# PR5005V1_3.net
KiCad netlist of a schematic drawn in EAGLE
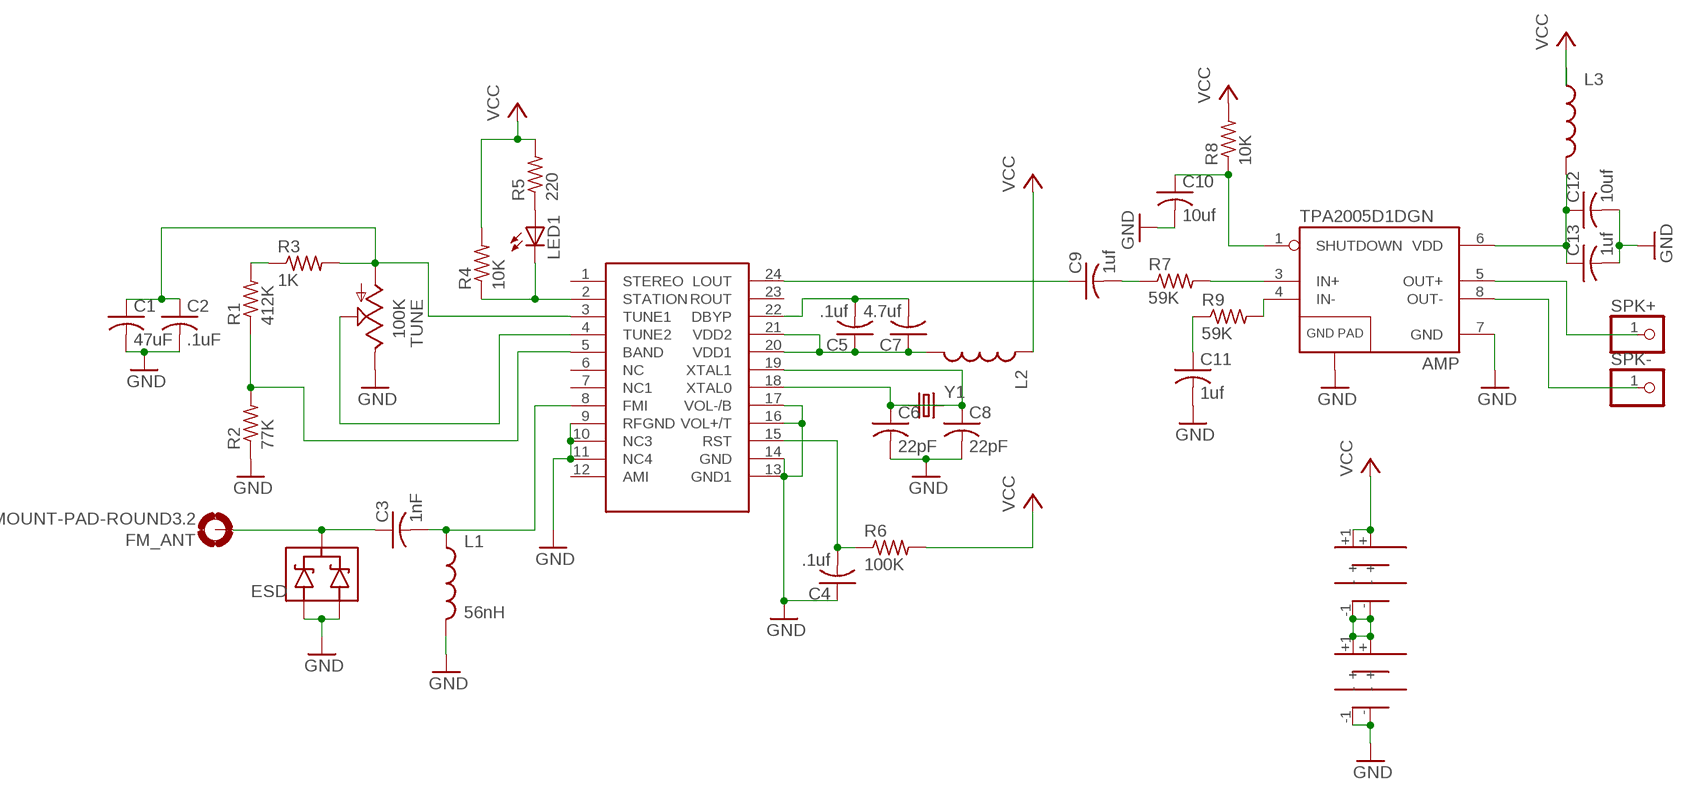
[diagram p0: schematic, sheet 1]

(export (version "E")
  (design (tool "Eeschema 10.0.6"))
  (components
    (comp (ref "AMP")
      (value "TPA2005D1DGN")
      (footprint "eagle-import:POWER-SOP8")
      (libsource (lib "eagle-import") (part "TPA2005D1DGN"))
    )
    (comp (ref "C1")
      (value "47uF")
      (footprint "eagle-import:C0603")
      (libsource (lib "eagle-import") (part "C-USC0603"))
    )
    (comp (ref "C2")
      (value ".1uF")
      (footprint "eagle-import:C0603")
      (libsource (lib "eagle-import") (part "C-USC0603"))
    )
    (comp (ref "C3")
      (value "1nF")
      (footprint "eagle-import:C0603")
      (libsource (lib "eagle-import") (part "C-USC0603"))
    )
    (comp (ref "C4")
      (value ".1uf")
      (footprint "eagle-import:C0603")
      (libsource (lib "eagle-import") (part "C-USC0603"))
    )
    (comp (ref "C5")
      (value ".1uf")
      (footprint "eagle-import:C0603")
      (libsource (lib "eagle-import") (part "C-USC0603"))
    )
    (comp (ref "C6")
      (value "22pF")
      (footprint "eagle-import:C0603")
      (libsource (lib "eagle-import") (part "C-USC0603"))
    )
    (comp (ref "C7")
      (value "4.7uf")
      (footprint "eagle-import:C0603")
      (libsource (lib "eagle-import") (part "C-USC0603"))
    )
    (comp (ref "C8")
      (value "22pF")
      (footprint "eagle-import:C0603")
      (libsource (lib "eagle-import") (part "C-USC0603"))
    )
    (comp (ref "C9")
      (value "1uf")
      (footprint "eagle-import:C0603")
      (libsource (lib "eagle-import") (part "C-USC0603"))
    )
    (comp (ref "C10")
      (value "10uf")
      (footprint "eagle-import:C0603")
      (libsource (lib "eagle-import") (part "C-USC0603"))
    )
    (comp (ref "C11")
      (value "1uf")
      (footprint "eagle-import:C0603")
      (libsource (lib "eagle-import") (part "C-USC0603"))
    )
    (comp (ref "C12")
      (value "10uf")
      (footprint "eagle-import:C0603")
      (libsource (lib "eagle-import") (part "C-USC0603"))
    )
    (comp (ref "C13")
      (value "1uf")
      (footprint "eagle-import:C0603")
      (libsource (lib "eagle-import") (part "C-USC0603"))
    )
    (comp (ref "ESD")
      (value "MMBZ27VCLT1")
      (footprint "eagle-import:SOT23-3")
      (libsource (lib "eagle-import") (part "MMBZ27VCLT1"))
    )
    (comp (ref "FM_ANT")
      (value "MOUNT-PAD-ROUND3.2")
      (footprint "eagle-import:3,2-PAD")
      (libsource (lib "eagle-import") (part "MOUNT-PAD-ROUND3.2"))
    )
    (comp (ref "L1")
      (value "56nH")
      (footprint "eagle-import:0603")
      (libsource (lib "eagle-import") (part "INDUCTOR0603"))
    )
    (comp (ref "L2")
      (value "INDUCTOR0603")
      (footprint "eagle-import:0603")
      (libsource (lib "eagle-import") (part "INDUCTOR0603"))
    )
    (comp (ref "L3")
      (value "INDUCTOR0603")
      (footprint "eagle-import:0603")
      (libsource (lib "eagle-import") (part "INDUCTOR0603"))
    )
    (comp (ref "LED1")
      (value "LEDCHIP-LED0603")
      (footprint "eagle-import:CHIP-LED0603")
      (libsource (lib "eagle-import") (part "LEDCHIP-LED0603"))
    )
    (comp (ref "R1")
      (value "412K")
      (footprint "eagle-import:R0603")
      (libsource (lib "eagle-import") (part "R-US_R0603"))
    )
    (comp (ref "R2")
      (value "77K")
      (footprint "eagle-import:R0603")
      (libsource (lib "eagle-import") (part "R-US_R0603"))
    )
    (comp (ref "R3")
      (value "1K")
      (footprint "eagle-import:R0603")
      (libsource (lib "eagle-import") (part "R-US_R0603"))
    )
    (comp (ref "R4")
      (value "10K")
      (footprint "eagle-import:R0603")
      (libsource (lib "eagle-import") (part "R-US_R0603"))
    )
    (comp (ref "R5")
      (value "220")
      (footprint "eagle-import:R0603")
      (libsource (lib "eagle-import") (part "R-US_R0603"))
    )
    (comp (ref "R6")
      (value "100K")
      (footprint "eagle-import:R0603")
      (libsource (lib "eagle-import") (part "R-US_R0603"))
    )
    (comp (ref "R7")
      (value "59K")
      (footprint "eagle-import:R0603")
      (libsource (lib "eagle-import") (part "R-US_R0603"))
    )
    (comp (ref "R8")
      (value "10K")
      (footprint "eagle-import:R0603")
      (libsource (lib "eagle-import") (part "R-US_R0603"))
    )
    (comp (ref "R9")
      (value "59K")
      (footprint "eagle-import:R0603")
      (libsource (lib "eagle-import") (part "R-US_R0603"))
    )
    (comp (ref "SI1")
      (value "SI4831-SSOP-24")
      (footprint "eagle-import:SI4831-SSOP-24")
      (libsource (lib "eagle-import") (part "SI4831-SSOP-24"))
    )
    (comp (ref "SPK+")
      (value "PINHD-1X1")
      (footprint "eagle-import:1X01")
      (libsource (lib "eagle-import") (part "PINHD-1X1"))
    )
    (comp (ref "SPK-")
      (value "PINHD-1X1")
      (footprint "eagle-import:1X01")
      (libsource (lib "eagle-import") (part "PINHD-1X1"))
    )
    (comp (ref "TUNE")
      (value "100K")
      (footprint "eagle-import:6MM")
      (libsource (lib "eagle-import") (part "TRIM"))
    )
    (comp (ref "U$1")
      (value "MPD-BK-92-AA-CLIP")
      (footprint "eagle-import:MPD-BK-92-AA-CLIP")
      (libsource (lib "eagle-import") (part "MPD-BK-92-AA-CLIP"))
    )
    (comp (ref "U$2")
      (value "MPD-BK-92-AA-CLIP")
      (footprint "eagle-import:MPD-BK-92-AA-CLIP")
      (libsource (lib "eagle-import") (part "MPD-BK-92-AA-CLIP"))
    )
    (comp (ref "Y1")
      (value "CRYSTAL32-SMD")
      (footprint "eagle-import:CRYSTAL-32KHZ-SMD")
      (libsource (lib "eagle-import") (part "CRYSTAL32-SMD"))
    )
  )
  (nets
    (net (code "1") (name "GND") (class "Default")
      (node (ref "AMP") (pin "7") (pinfunction "GND_7") (pintype "power_in"))
      (node (ref "AMP") (pin "9") (pinfunction "GND_9") (pintype "power_in"))
      (node (ref "C1") (pin "2") (pinfunction "2_2") (pintype "passive"))
      (node (ref "C10") (pin "2") (pinfunction "2_2") (pintype "passive"))
      (node (ref "C11") (pin "2") (pinfunction "2_2") (pintype "passive"))
      (node (ref "C12") (pin "2") (pinfunction "2_2") (pintype "passive"))
      (node (ref "C13") (pin "2") (pinfunction "2_2") (pintype "passive"))
      (node (ref "C2") (pin "2") (pinfunction "2_2") (pintype "passive"))
      (node (ref "C4") (pin "1") (pinfunction "1_1") (pintype "passive"))
      (node (ref "C6") (pin "2") (pinfunction "2_2") (pintype "passive"))
      (node (ref "C8") (pin "2") (pinfunction "2_2") (pintype "passive"))
      (node (ref "ESD") (pin "1") (pinfunction "A1_1") (pintype "passive"))
      (node (ref "ESD") (pin "2") (pinfunction "A2_2") (pintype "passive"))
      (node (ref "L1") (pin "2") (pinfunction "2_2") (pintype "passive"))
      (node (ref "R2") (pin "1") (pinfunction "1_1") (pintype "passive"))
      (node (ref "SI1") (pin "10") (pinfunction "NC3_10") (pintype "bidirectional"))
      (node (ref "SI1") (pin "11") (pinfunction "NC4_11") (pintype "bidirectional"))
      (node (ref "SI1") (pin "13") (pinfunction "GND1_13") (pintype "bidirectional"))
      (node (ref "SI1") (pin "14") (pinfunction "GND_14") (pintype "bidirectional"))
      (node (ref "SI1") (pin "16") (pinfunction "VOL+/T_16") (pintype "bidirectional"))
      (node (ref "SI1") (pin "17") (pinfunction "VOL-/B_17") (pintype "bidirectional"))
      (node (ref "SI1") (pin "9") (pinfunction "RFGND_9") (pintype "bidirectional"))
      (node (ref "TUNE") (pin "E") (pinfunction "E_E") (pintype "passive"))
      (node (ref "U$2") (pin "-") (pinfunction "-_-") (pintype "bidirectional"))
      (node (ref "U$2") (pin "-1") (pinfunction "-_-1") (pintype "bidirectional"))
    )
    (net (code "2") (name "Net-(AMP-IN+)") (class "Default")
      (node (ref "AMP") (pin "3") (pinfunction "IN+_3") (pintype "bidirectional"))
      (node (ref "R7") (pin "2") (pinfunction "2_2") (pintype "passive"))
    )
    (net (code "3") (name "Net-(AMP-IN-)") (class "Default")
      (node (ref "AMP") (pin "4") (pinfunction "IN-_4") (pintype "bidirectional"))
      (node (ref "R9") (pin "2") (pinfunction "2_2") (pintype "passive"))
    )
    (net (code "4") (name "Net-(AMP-OUT+)") (class "Default")
      (node (ref "AMP") (pin "5") (pinfunction "OUT+_5") (pintype "bidirectional"))
      (node (ref "SPK+") (pin "1") (pinfunction "1_1") (pintype "passive"))
    )
    (net (code "5") (name "Net-(AMP-OUT-)") (class "Default")
      (node (ref "AMP") (pin "8") (pinfunction "OUT-_8") (pintype "bidirectional"))
      (node (ref "SPK-") (pin "1") (pinfunction "1_1") (pintype "passive"))
    )
    (net (code "6") (name "Net-(AMP-SHUTDOWN)") (class "Default")
      (node (ref "AMP") (pin "1") (pinfunction "SHUTDOWN_1") (pintype "input"))
      (node (ref "C10") (pin "1") (pinfunction "1_1") (pintype "passive"))
      (node (ref "R8") (pin "1") (pinfunction "1_1") (pintype "passive"))
    )
    (net (code "7") (name "Net-(AMP-VDD)") (class "Default")
      (node (ref "AMP") (pin "6") (pinfunction "VDD_6") (pintype "power_in"))
      (node (ref "C12") (pin "1") (pinfunction "1_1") (pintype "passive"))
      (node (ref "C13") (pin "1") (pinfunction "1_1") (pintype "passive"))
      (node (ref "L3") (pin "2") (pinfunction "2_2") (pintype "passive"))
    )
    (net (code "8") (name "Net-(C9-Pad2)") (class "Default")
      (node (ref "C9") (pin "2") (pinfunction "2_2") (pintype "passive"))
      (node (ref "R7") (pin "1") (pinfunction "1_1") (pintype "passive"))
    )
    (net (code "9") (name "Net-(C11-Pad1)") (class "Default")
      (node (ref "C11") (pin "1") (pinfunction "1_1") (pintype "passive"))
      (node (ref "R9") (pin "1") (pinfunction "1_1") (pintype "passive"))
    )
    (net (code "10") (name "Net-(ESD-C)") (class "Default")
      (node (ref "C3") (pin "1") (pinfunction "1_1") (pintype "passive"))
      (node (ref "ESD") (pin "3") (pinfunction "C_3") (pintype "passive"))
      (node (ref "FM_ANT") (pin "B3,2") (pinfunction "MOUNT_B3,2") (pintype "passive"))
    )
    (net (code "11") (name "Net-(LED1-PadA)") (class "Default")
      (node (ref "LED1") (pin "A") (pinfunction "A_A") (pintype "passive"))
      (node (ref "R5") (pin "1") (pinfunction "1_1") (pintype "passive"))
    )
    (net (code "12") (name "Net-(R1-Pad2)") (class "Default")
      (node (ref "R1") (pin "2") (pinfunction "2_2") (pintype "passive"))
      (node (ref "R3") (pin "1") (pinfunction "1_1") (pintype "passive"))
    )
    (net (code "13") (name "Net-(SI1-BAND)") (class "Default")
      (node (ref "R1") (pin "1") (pinfunction "1_1") (pintype "passive"))
      (node (ref "R2") (pin "2") (pinfunction "2_2") (pintype "passive"))
      (node (ref "SI1") (pin "5") (pinfunction "BAND_5") (pintype "bidirectional"))
    )
    (net (code "14") (name "Net-(SI1-DBYP)") (class "Default")
      (node (ref "C5") (pin "2") (pinfunction "2_2") (pintype "passive"))
      (node (ref "C7") (pin "2") (pinfunction "2_2") (pintype "passive"))
      (node (ref "SI1") (pin "22") (pinfunction "DBYP_22") (pintype "bidirectional"))
    )
    (net (code "15") (name "Net-(SI1-FMI)") (class "Default")
      (node (ref "C3") (pin "2") (pinfunction "2_2") (pintype "passive"))
      (node (ref "L1") (pin "1") (pinfunction "1_1") (pintype "passive"))
      (node (ref "SI1") (pin "8") (pinfunction "FMI_8") (pintype "bidirectional"))
    )
    (net (code "16") (name "Net-(SI1-LOUT)") (class "Default")
      (node (ref "C9") (pin "1") (pinfunction "1_1") (pintype "passive"))
      (node (ref "SI1") (pin "24") (pinfunction "LOUT_24") (pintype "bidirectional"))
    )
    (net (code "17") (name "Net-(SI1-RST)") (class "Default")
      (node (ref "C4") (pin "2") (pinfunction "2_2") (pintype "passive"))
      (node (ref "R6") (pin "1") (pinfunction "1_1") (pintype "passive"))
      (node (ref "SI1") (pin "15") (pinfunction "RST_15") (pintype "bidirectional"))
    )
    (net (code "18") (name "Net-(SI1-STATION)") (class "Default")
      (node (ref "LED1") (pin "C") (pinfunction "C_C") (pintype "passive"))
      (node (ref "R4") (pin "1") (pinfunction "1_1") (pintype "passive"))
      (node (ref "SI1") (pin "2") (pinfunction "STATION_2") (pintype "bidirectional"))
    )
    (net (code "19") (name "Net-(SI1-TUNE1)") (class "Default")
      (node (ref "C1") (pin "1") (pinfunction "1_1") (pintype "passive"))
      (node (ref "C2") (pin "1") (pinfunction "1_1") (pintype "passive"))
      (node (ref "R3") (pin "2") (pinfunction "2_2") (pintype "passive"))
      (node (ref "SI1") (pin "3") (pinfunction "TUNE1_3") (pintype "bidirectional"))
      (node (ref "TUNE") (pin "A") (pinfunction "A_A") (pintype "passive"))
    )
    (net (code "20") (name "Net-(SI1-TUNE2)") (class "Default")
      (node (ref "SI1") (pin "4") (pinfunction "TUNE2_4") (pintype "bidirectional"))
      (node (ref "TUNE") (pin "S") (pinfunction "S_S") (pintype "passive"))
    )
    (net (code "21") (name "Net-(SI1-VDD1)") (class "Default")
      (node (ref "C5") (pin "1") (pinfunction "1_1") (pintype "passive"))
      (node (ref "C7") (pin "1") (pinfunction "1_1") (pintype "passive"))
      (node (ref "L2") (pin "2") (pinfunction "2_2") (pintype "passive"))
      (node (ref "SI1") (pin "20") (pinfunction "VDD1_20") (pintype "bidirectional"))
      (node (ref "SI1") (pin "21") (pinfunction "VDD2_21") (pintype "bidirectional"))
    )
    (net (code "22") (name "Net-(SI1-XTAL0)") (class "Default")
      (node (ref "C6") (pin "1") (pinfunction "1_1") (pintype "passive"))
      (node (ref "SI1") (pin "18") (pinfunction "XTAL0_18") (pintype "bidirectional"))
      (node (ref "Y1") (pin "X2") (pinfunction "2_X2") (pintype "passive"))
    )
    (net (code "23") (name "Net-(SI1-XTAL1)") (class "Default")
      (node (ref "C8") (pin "1") (pinfunction "1_1") (pintype "passive"))
      (node (ref "SI1") (pin "19") (pinfunction "XTAL1_19") (pintype "bidirectional"))
      (node (ref "Y1") (pin "X1") (pinfunction "1_X1") (pintype "passive"))
    )
    (net (code "24") (name "Net-(U$1---Pad-1)") (class "Default")
      (node (ref "U$1") (pin "-") (pinfunction "-_-") (pintype "bidirectional"))
      (node (ref "U$1") (pin "-1") (pinfunction "-_-1") (pintype "bidirectional"))
      (node (ref "U$2") (pin "+") (pinfunction "+_+") (pintype "bidirectional"))
      (node (ref "U$2") (pin "+1") (pinfunction "+_+1") (pintype "bidirectional"))
    )
    (net (code "25") (name "VCC") (class "Default")
      (node (ref "L2") (pin "1") (pinfunction "1_1") (pintype "passive"))
      (node (ref "L3") (pin "1") (pinfunction "1_1") (pintype "passive"))
      (node (ref "R4") (pin "2") (pinfunction "2_2") (pintype "passive"))
      (node (ref "R5") (pin "2") (pinfunction "2_2") (pintype "passive"))
      (node (ref "R6") (pin "2") (pinfunction "2_2") (pintype "passive"))
      (node (ref "R8") (pin "2") (pinfunction "2_2") (pintype "passive"))
      (node (ref "U$1") (pin "+") (pinfunction "+_+") (pintype "bidirectional"))
      (node (ref "U$1") (pin "+1") (pinfunction "+_+1") (pintype "bidirectional"))
    )
    (net (code "26") (name "unconnected-(SI1-AMI-Pad12)") (class "Default")
      (node (ref "SI1") (pin "12") (pinfunction "AMI_12") (pintype "bidirectional"))
    )
    (net (code "27") (name "unconnected-(SI1-NC-Pad6)") (class "Default")
      (node (ref "SI1") (pin "6") (pinfunction "NC_6") (pintype "bidirectional"))
    )
    (net (code "28") (name "unconnected-(SI1-NC1-Pad7)") (class "Default")
      (node (ref "SI1") (pin "7") (pinfunction "NC1_7") (pintype "bidirectional"))
    )
    (net (code "29") (name "unconnected-(SI1-ROUT-Pad23)") (class "Default")
      (node (ref "SI1") (pin "23") (pinfunction "ROUT_23") (pintype "bidirectional"))
    )
    (net (code "30") (name "unconnected-(SI1-STEREO-Pad1)") (class "Default")
      (node (ref "SI1") (pin "1") (pinfunction "STEREO_1") (pintype "bidirectional"))
    )
  )
)
